# CANViaRJ45AdapterBoard.net
KiCad netlist of a schematic drawn in EasyEDA
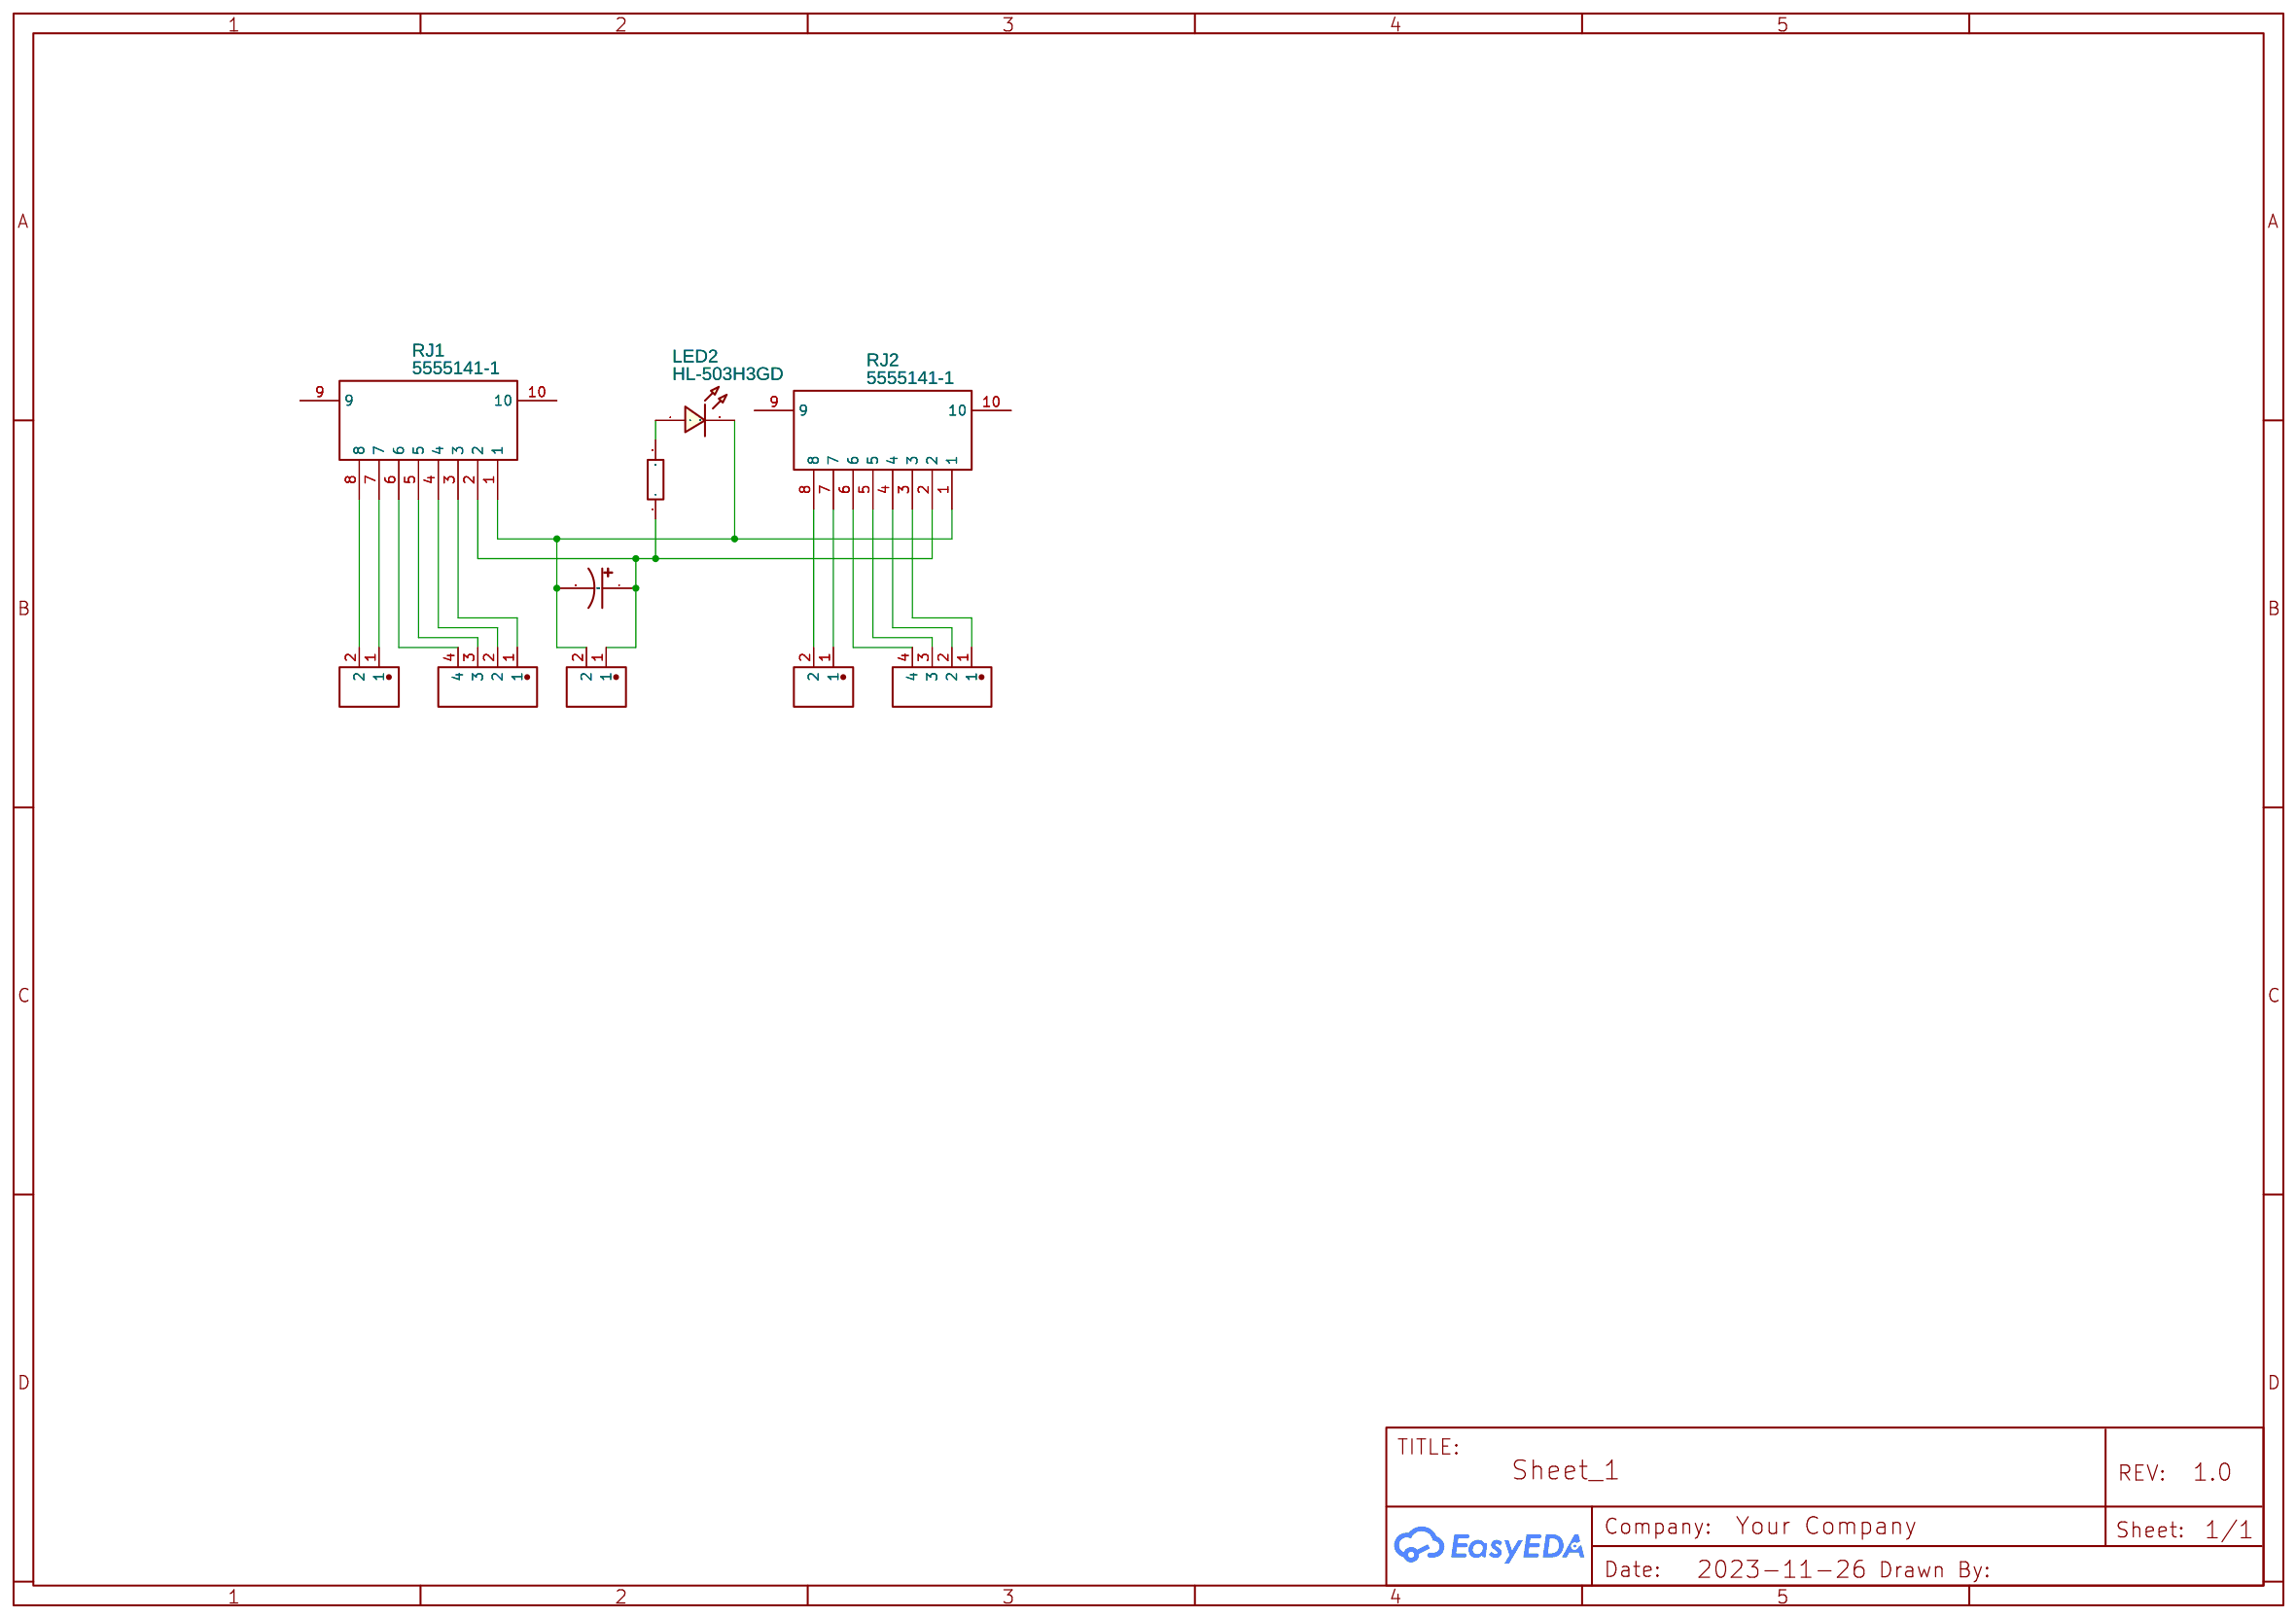
[diagram p0: schematic sheet]

(export (version "E")
  (design (tool "Eeschema 10.0.6"))
  (components
    (comp (ref "C1")
      (value "1000uF")
      (fields
        (field (name "Manufacturer Part") "GF1C102MF160A00CV0")
        (field (name "Manufacturer") "HUAWEI(华威集团)")
      )
      (libsource (lib "") (part "GF1C102MF160A00CV0"))
    )
    (comp (ref "CN1")
      (value "XY111B-5.08-2P")
      (fields (field (name "Manufacturer") "XINLAIYA(新莱亚)"))
      (libsource (lib "") (part "XY111B-5.08-2P"))
    )
    (comp (ref "CN2")
      (value "XY111B-5.08-2P")
      (fields (field (name "Manufacturer") "XINLAIYA(新莱亚)"))
      (libsource (lib "") (part "XY111B-5.08-2P"))
    )
    (comp (ref "CN3")
      (value "XY111B-5.08-2P")
      (fields (field (name "Manufacturer") "XINLAIYA(新莱亚)"))
      (libsource (lib "") (part "XY111B-5.08-2P"))
    )
    (comp (ref "CN4")
      (value "KF243A-5.0-4P")
      (fields (field (name "Manufacturer") "KEFA(科发)"))
      (libsource (lib "") (part "KF243A-5.0-4P"))
    )
    (comp (ref "CN5")
      (value "KF243A-5.0-4P")
      (fields (field (name "Manufacturer") "KEFA(科发)"))
      (libsource (lib "") (part "KF243A-5.0-4P"))
    )
    (comp (ref "LED2")
      (value "HL-503H3GD")
      (fields (field (name "Manufacturer") "HONGLITRONIC(鸿利光电)"))
      (libsource (lib "") (part "HL-503H3GD"))
    )
    (comp (ref "RJ1")
      (value "5555141-1")
      (fields (field (name "Manufacturer") "TE Connectivity(美国泰科)"))
      (libsource (lib "") (part "5555141-1"))
    )
    (comp (ref "RJ2")
      (value "5555141-1")
      (fields (field (name "Manufacturer") "TE Connectivity(美国泰科)"))
      (libsource (lib "") (part "5555141-1"))
    )
    (comp (ref "U1")
      (value "600Ω")
      (fields (field (name "Manufacturer Part") "MO1W-600Ω±5%-6T63") (field (name "Manufacturer") "VO(翔胜)"))
      (libsource (lib "") (part "MO1W-600Ω±5%-6T63"))
    )
  )
  (nets
    (net (code "1") (name "Net-(C1-Pad1)") (class "Default")
      (node (ref "C1") (pin "1") (pinfunction "1_1") (pintype "unspecified"))
      (node (ref "CN3") (pin "1") (pinfunction "1_1") (pintype "unspecified"))
      (node (ref "RJ1") (pin "2") (pinfunction "2_2") (pintype "unspecified"))
      (node (ref "RJ2") (pin "2") (pinfunction "2_2") (pintype "unspecified"))
      (node (ref "U1") (pin "1") (pinfunction "1_1") (pintype "unspecified"))
    )
    (net (code "2") (name "Net-(C1-Pad2)") (class "Default")
      (node (ref "C1") (pin "2") (pinfunction "2_2") (pintype "unspecified"))
      (node (ref "CN3") (pin "2") (pinfunction "2_2") (pintype "unspecified"))
      (node (ref "LED2") (pin "2") (pinfunction "2_2") (pintype "unspecified"))
      (node (ref "RJ1") (pin "1") (pinfunction "1_1") (pintype "unspecified"))
      (node (ref "RJ2") (pin "1") (pinfunction "1_1") (pintype "unspecified"))
    )
    (net (code "3") (name "Net-(CN1-Pad1)") (class "Default")
      (node (ref "CN1") (pin "1") (pinfunction "1_1") (pintype "unspecified"))
      (node (ref "RJ1") (pin "7") (pinfunction "7_7") (pintype "unspecified"))
    )
    (net (code "4") (name "Net-(CN1-Pad2)") (class "Default")
      (node (ref "CN1") (pin "2") (pinfunction "2_2") (pintype "unspecified"))
      (node (ref "RJ1") (pin "8") (pinfunction "8_8") (pintype "unspecified"))
    )
    (net (code "5") (name "Net-(CN2-Pad1)") (class "Default")
      (node (ref "CN2") (pin "1") (pinfunction "1_1") (pintype "unspecified"))
      (node (ref "RJ2") (pin "7") (pinfunction "7_7") (pintype "unspecified"))
    )
    (net (code "6") (name "Net-(CN2-Pad2)") (class "Default")
      (node (ref "CN2") (pin "2") (pinfunction "2_2") (pintype "unspecified"))
      (node (ref "RJ2") (pin "8") (pinfunction "8_8") (pintype "unspecified"))
    )
    (net (code "7") (name "Net-(CN4-Pad1)") (class "Default")
      (node (ref "CN4") (pin "1") (pinfunction "1_1") (pintype "unspecified"))
      (node (ref "RJ1") (pin "3") (pinfunction "3_3") (pintype "unspecified"))
    )
    (net (code "8") (name "Net-(CN4-Pad2)") (class "Default")
      (node (ref "CN4") (pin "2") (pinfunction "2_2") (pintype "unspecified"))
      (node (ref "RJ1") (pin "4") (pinfunction "4_4") (pintype "unspecified"))
    )
    (net (code "9") (name "Net-(CN4-Pad3)") (class "Default")
      (node (ref "CN4") (pin "3") (pinfunction "3_3") (pintype "unspecified"))
      (node (ref "RJ1") (pin "5") (pinfunction "5_5") (pintype "unspecified"))
    )
    (net (code "10") (name "Net-(CN4-Pad4)") (class "Default")
      (node (ref "CN4") (pin "4") (pinfunction "4_4") (pintype "unspecified"))
      (node (ref "RJ1") (pin "6") (pinfunction "6_6") (pintype "unspecified"))
    )
    (net (code "11") (name "Net-(CN5-Pad1)") (class "Default")
      (node (ref "CN5") (pin "1") (pinfunction "1_1") (pintype "unspecified"))
      (node (ref "RJ2") (pin "3") (pinfunction "3_3") (pintype "unspecified"))
    )
    (net (code "12") (name "Net-(CN5-Pad2)") (class "Default")
      (node (ref "CN5") (pin "2") (pinfunction "2_2") (pintype "unspecified"))
      (node (ref "RJ2") (pin "4") (pinfunction "4_4") (pintype "unspecified"))
    )
    (net (code "13") (name "Net-(CN5-Pad3)") (class "Default")
      (node (ref "CN5") (pin "3") (pinfunction "3_3") (pintype "unspecified"))
      (node (ref "RJ2") (pin "5") (pinfunction "5_5") (pintype "unspecified"))
    )
    (net (code "14") (name "Net-(CN5-Pad4)") (class "Default")
      (node (ref "CN5") (pin "4") (pinfunction "4_4") (pintype "unspecified"))
      (node (ref "RJ2") (pin "6") (pinfunction "6_6") (pintype "unspecified"))
    )
    (net (code "15") (name "Net-(LED2-Pad1)") (class "Default")
      (node (ref "LED2") (pin "1") (pinfunction "1_1") (pintype "unspecified"))
      (node (ref "U1") (pin "2") (pinfunction "2_2") (pintype "unspecified"))
    )
    (net (code "16") (name "unconnected-(RJ1-Pad9)") (class "Default")
      (node (ref "RJ1") (pin "9") (pinfunction "9_9") (pintype "unspecified"))
    )
    (net (code "17") (name "unconnected-(RJ1-Pad10)") (class "Default")
      (node (ref "RJ1") (pin "10") (pinfunction "10_10") (pintype "unspecified"))
    )
    (net (code "18") (name "unconnected-(RJ2-Pad9)") (class "Default")
      (node (ref "RJ2") (pin "9") (pinfunction "9_9") (pintype "unspecified"))
    )
    (net (code "19") (name "unconnected-(RJ2-Pad10)") (class "Default")
      (node (ref "RJ2") (pin "10") (pinfunction "10_10") (pintype "unspecified"))
    )
  )
)
